# 12V_SMPS.net
KiCad netlist of a schematic drawn in Altium Designer
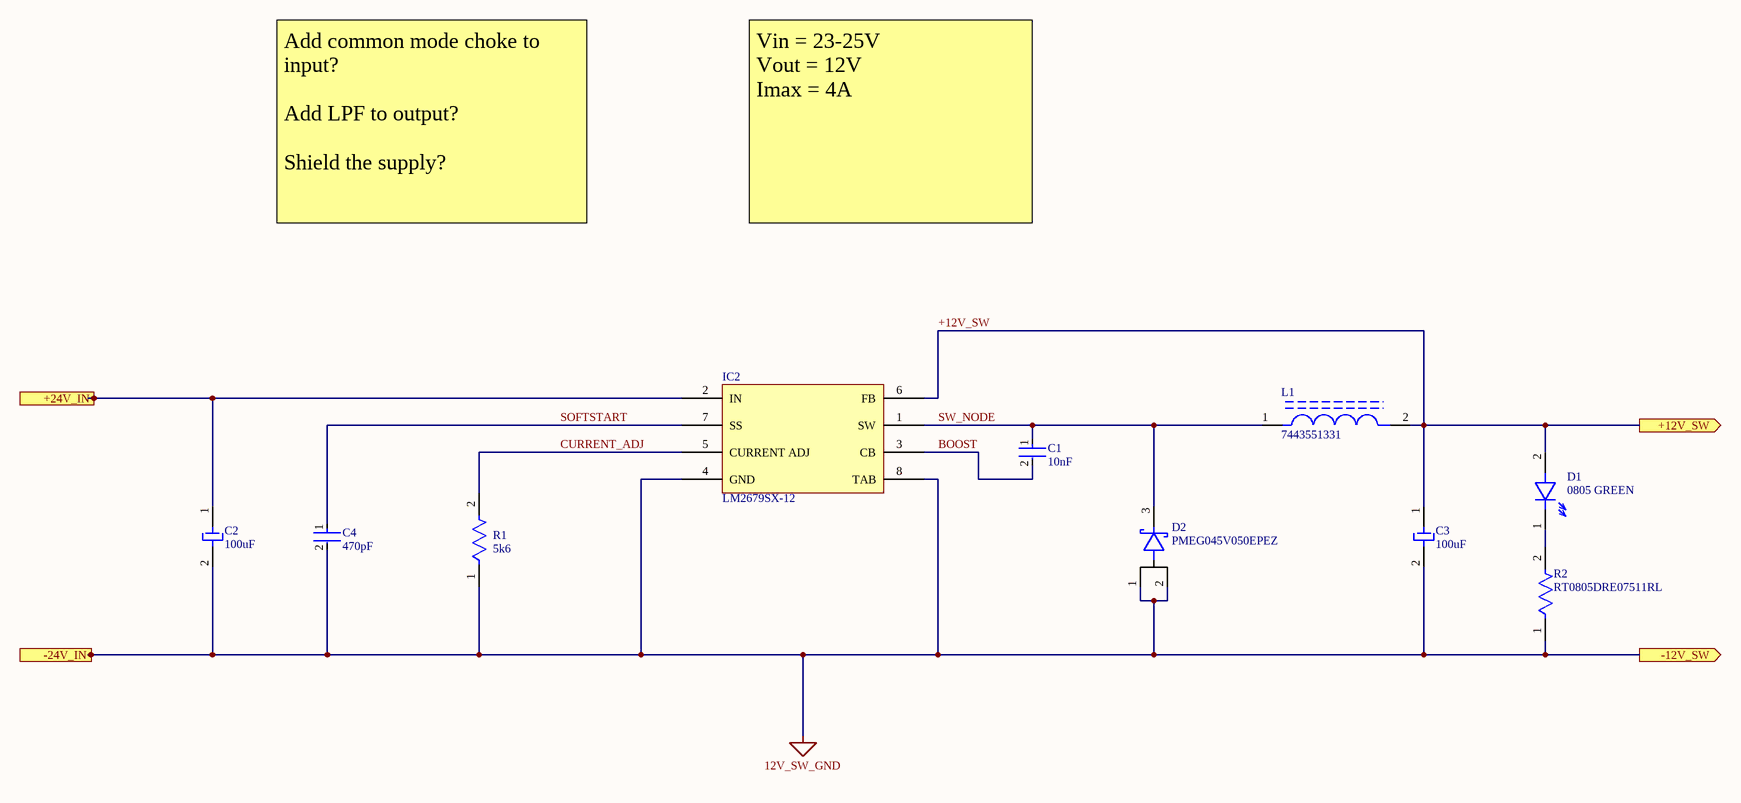
[diagram p0: 12V SMPS.SchDoc]

(export (version "E")
  (design (tool "Eeschema 10.0.6"))
  (components
    (comp (ref "C1")
      (value "10nF")
      (footprint "FP-C0805C-DN-MFG")
      (description "C0805 10,000 pF C0G 30ppm/°C 5.00% 50 V")
      (fields
        (field (name "OCTOPART") "https://octopart.com/c0805c103j5gac-kemet-22233108")
        (field (name "MANUFACTURER") "KEMET")
      )
      (libsource (lib "Altium Content Vault") (part "b4654b650e69147ec39a6b967a45e02"))
    )
    (comp (ref "C2")
      (value "100uF")
      (footprint "AHA1010101M040R")
      (description "Kyocera AHA1010101M040R")
      (libsource (lib "12V SMPS") (part "100uF"))
    )
    (comp (ref "C3")
      (value "100uF")
      (footprint "AHA1010101M040R")
      (description "Kyocera AHA1010101M040R")
      (libsource (lib "12V SMPS") (part "100uF"))
    )
    (comp (ref "C4")
      (value "470pF")
      (footprint "FP-C0805C-DN-MFG")
      (description "C0805 470 pF C0G 30ppm/°C 5.00% 50 V")
      (fields
        (field (name "MANUFACTURER") "KEMET")
        (field (name "OCTOPART") "https://octopart.com/c0805c471j5gac-kemet-1364888")
      )
      (libsource (lib "Altium Content Vault") (part "b4654b650e69147ec39a6b967a45e02"))
    )
    (comp (ref "D1")
      (value "0805 GREEN")
      (footprint "0805 LED")
      (description "Wurth Electronics 150080VS75000")
      (libsource (lib "12V SMPS") (part "0805 LED"))
    )
    (comp (ref "D2")
      (value "PMEG045V050EPEZ")
      (footprint "PMEG045V050EPE")
      (libsource (lib "12V SMPS") (part "PMEG045V050EPEZ"))
    )
    (comp (ref "IC2")
      (value "LM2679SX-12")
      (footprint "TS7B_M")
      (description "LM2679SX-12/NOPB")
      (libsource (lib "12V SMPS") (part "LM2679SX-12"))
    )
    (comp (ref "L1")
      (value "7443551331")
      (footprint "7443551331 33uH")
      (description "Wurth Electronics 7443551331")
      (libsource (lib "12V SMPS") (part "7443551331"))
    )
    (comp (ref "R1")
      (value "5k6")
      (footprint "FP-CRCW0805-e3-IPC_A")
      (description "RES Thick Film, 5.6kΩ, 1%, 0.125W, 100ppm/°C, 0805")
      (fields (field (name "TOLERANCE") "1%"))
      (libsource (lib "Altium Content Vault") (part "1029c3af85768c4190bb7ad29bc67b5"))
    )
    (comp (ref "R2")
      (value "RT0805DRE07511RL")
      (footprint "FP-RT0805-MFG")
      (description "RES SMD 511 OHM 0.5% 1/8W 0805")
      (fields
        (field (name "MANUFACTURER") "Yageo")
        (field (name "OCTOPART") "https://octopart.com/rt0805dre07511rl-yageo-1369364")
      )
      (libsource (lib "Altium Content Vault") (part "1029c3af85768c4190bb7ad29bc67b5"))
    )
  )
  (nets
    (net (code "1") (name "/+12V_SW") (class "Default")
      (node (ref "C3") (pin "1") (pintype "passive"))
      (node (ref "D1") (pin "2") (pinfunction "Anode_2") (pintype "passive"))
      (node (ref "IC2") (pin "6") (pinfunction "FB_6") (pintype "passive"))
      (node (ref "L1") (pin "2") (pintype "passive"))
    )
    (net (code "2") (name "/+24V_IN") (class "Default")
      (node (ref "C2") (pin "1") (pintype "passive"))
      (node (ref "IC2") (pin "2") (pinfunction "IN_2") (pintype "passive"))
    )
    (net (code "3") (name "/BOOST") (class "Default")
      (node (ref "C1") (pin "2") (pinfunction "2_2") (pintype "passive"))
      (node (ref "IC2") (pin "3") (pinfunction "CB_3") (pintype "passive"))
    )
    (net (code "4") (name "/CURRENT_ADJ") (class "Default")
      (node (ref "IC2") (pin "5") (pinfunction "CURRENT_ADJ_5") (pintype "passive"))
      (node (ref "R1") (pin "2") (pinfunction "2_2") (pintype "passive"))
    )
    (net (code "5") (name "/SOFTSTART") (class "Default")
      (node (ref "C4") (pin "1") (pinfunction "1_1") (pintype "passive"))
      (node (ref "IC2") (pin "7") (pinfunction "SS_7") (pintype "passive"))
    )
    (net (code "6") (name "/SW_NODE") (class "Default")
      (node (ref "C1") (pin "1") (pinfunction "1_1") (pintype "passive"))
      (node (ref "D2") (pin "3") (pinfunction "Cathode_3") (pintype "passive"))
      (node (ref "IC2") (pin "1") (pinfunction "SW_1") (pintype "passive"))
      (node (ref "L1") (pin "1") (pintype "passive"))
    )
    (net (code "7") (name "12V_SW_GND") (class "Default")
      (node (ref "C2") (pin "2") (pintype "passive"))
      (node (ref "C3") (pin "2") (pintype "passive"))
      (node (ref "C4") (pin "2") (pinfunction "2_2") (pintype "passive"))
      (node (ref "D2") (pin "1") (pinfunction "Anode_1") (pintype "passive"))
      (node (ref "D2") (pin "2") (pinfunction "Anode_2") (pintype "passive"))
      (node (ref "IC2") (pin "4") (pinfunction "GND_4") (pintype "passive"))
      (node (ref "IC2") (pin "8") (pinfunction "TAB_8") (pintype "passive"))
      (node (ref "R1") (pin "1") (pinfunction "1_1") (pintype "passive"))
      (node (ref "R2") (pin "1") (pinfunction "1_1") (pintype "passive"))
    )
    (net (code "8") (name "Net-(D1-Cathode)") (class "Default")
      (node (ref "D1") (pin "1") (pinfunction "Cathode_1") (pintype "passive"))
      (node (ref "R2") (pin "2") (pinfunction "2_2") (pintype "passive"))
    )
  )
)
